# LED_Schaltung.net
KiCad netlist of a schematic drawn in EAGLE
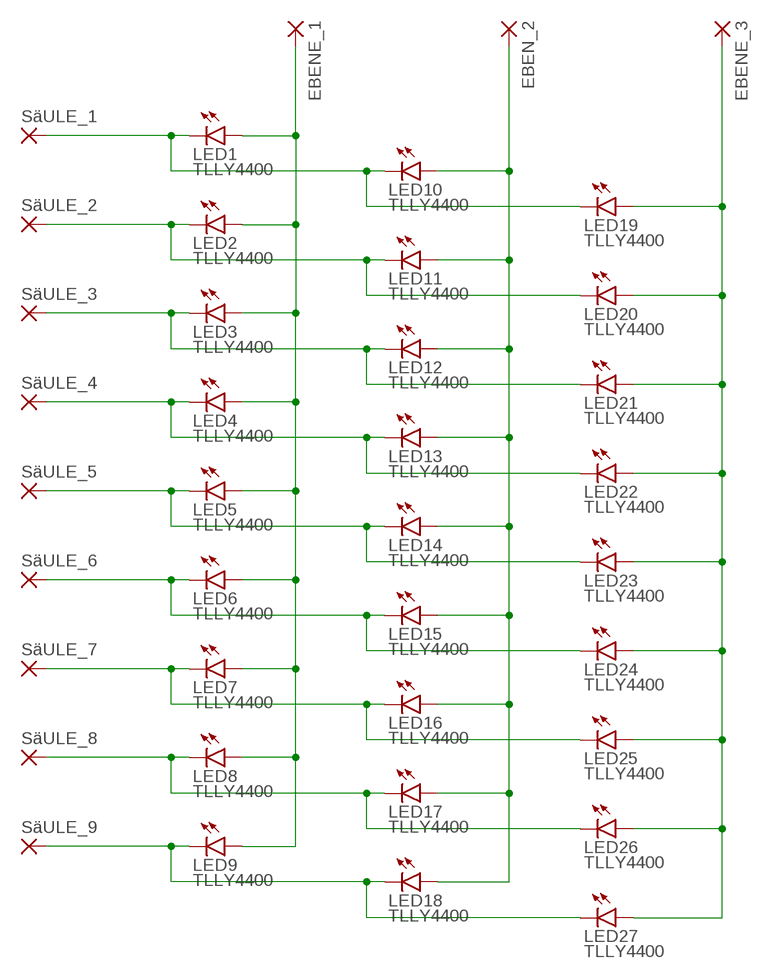
[diagram p0: schematic, sheet 1]

(export (version "E")
  (design (tool "Eeschema 10.0.6"))
  (components
    (comp (ref "EBENE_1")
      (value "2,54/1,0")
      (footprint "eagle-import:2,54_1,0")
      (libsource (lib "eagle-import") (part "2,54/1,0"))
    )
    (comp (ref "EBENE_3")
      (value "2,54/1,0")
      (footprint "eagle-import:2,54_1,0")
      (libsource (lib "eagle-import") (part "2,54/1,0"))
    )
    (comp (ref "EBEN_2")
      (value "2,54/1,0")
      (footprint "eagle-import:2,54_1,0")
      (libsource (lib "eagle-import") (part "2,54/1,0"))
    )
    (comp (ref "LED1")
      (value "TLLY4400")
      (footprint "eagle-import:LED3MM")
      (fields (field (name "MF") "VISHAY SEMICONDUCTOR"))
      (libsource (lib "eagle-import") (part "TLLY4400"))
    )
    (comp (ref "LED2")
      (value "TLLY4400")
      (footprint "eagle-import:LED3MM")
      (fields (field (name "MF") "VISHAY SEMICONDUCTOR"))
      (libsource (lib "eagle-import") (part "TLLY4400"))
    )
    (comp (ref "LED3")
      (value "TLLY4400")
      (footprint "eagle-import:LED3MM")
      (fields (field (name "MF") "VISHAY SEMICONDUCTOR"))
      (libsource (lib "eagle-import") (part "TLLY4400"))
    )
    (comp (ref "LED4")
      (value "TLLY4400")
      (footprint "eagle-import:LED3MM")
      (fields (field (name "MF") "VISHAY SEMICONDUCTOR"))
      (libsource (lib "eagle-import") (part "TLLY4400"))
    )
    (comp (ref "LED5")
      (value "TLLY4400")
      (footprint "eagle-import:LED3MM")
      (fields (field (name "MF") "VISHAY SEMICONDUCTOR"))
      (libsource (lib "eagle-import") (part "TLLY4400"))
    )
    (comp (ref "LED6")
      (value "TLLY4400")
      (footprint "eagle-import:LED3MM")
      (fields (field (name "MF") "VISHAY SEMICONDUCTOR"))
      (libsource (lib "eagle-import") (part "TLLY4400"))
    )
    (comp (ref "LED7")
      (value "TLLY4400")
      (footprint "eagle-import:LED3MM")
      (fields (field (name "MF") "VISHAY SEMICONDUCTOR"))
      (libsource (lib "eagle-import") (part "TLLY4400"))
    )
    (comp (ref "LED8")
      (value "TLLY4400")
      (footprint "eagle-import:LED3MM")
      (fields (field (name "MF") "VISHAY SEMICONDUCTOR"))
      (libsource (lib "eagle-import") (part "TLLY4400"))
    )
    (comp (ref "LED9")
      (value "TLLY4400")
      (footprint "eagle-import:LED3MM")
      (fields (field (name "MF") "VISHAY SEMICONDUCTOR"))
      (libsource (lib "eagle-import") (part "TLLY4400"))
    )
    (comp (ref "LED10")
      (value "TLLY4400")
      (footprint "eagle-import:LED3MM")
      (fields (field (name "MF") "VISHAY SEMICONDUCTOR"))
      (libsource (lib "eagle-import") (part "TLLY4400"))
    )
    (comp (ref "LED11")
      (value "TLLY4400")
      (footprint "eagle-import:LED3MM")
      (fields (field (name "MF") "VISHAY SEMICONDUCTOR"))
      (libsource (lib "eagle-import") (part "TLLY4400"))
    )
    (comp (ref "LED12")
      (value "TLLY4400")
      (footprint "eagle-import:LED3MM")
      (fields (field (name "MF") "VISHAY SEMICONDUCTOR"))
      (libsource (lib "eagle-import") (part "TLLY4400"))
    )
    (comp (ref "LED13")
      (value "TLLY4400")
      (footprint "eagle-import:LED3MM")
      (fields (field (name "MF") "VISHAY SEMICONDUCTOR"))
      (libsource (lib "eagle-import") (part "TLLY4400"))
    )
    (comp (ref "LED14")
      (value "TLLY4400")
      (footprint "eagle-import:LED3MM")
      (fields (field (name "MF") "VISHAY SEMICONDUCTOR"))
      (libsource (lib "eagle-import") (part "TLLY4400"))
    )
    (comp (ref "LED15")
      (value "TLLY4400")
      (footprint "eagle-import:LED3MM")
      (fields (field (name "MF") "VISHAY SEMICONDUCTOR"))
      (libsource (lib "eagle-import") (part "TLLY4400"))
    )
    (comp (ref "LED16")
      (value "TLLY4400")
      (footprint "eagle-import:LED3MM")
      (fields (field (name "MF") "VISHAY SEMICONDUCTOR"))
      (libsource (lib "eagle-import") (part "TLLY4400"))
    )
    (comp (ref "LED17")
      (value "TLLY4400")
      (footprint "eagle-import:LED3MM")
      (fields (field (name "MF") "VISHAY SEMICONDUCTOR"))
      (libsource (lib "eagle-import") (part "TLLY4400"))
    )
    (comp (ref "LED18")
      (value "TLLY4400")
      (footprint "eagle-import:LED3MM")
      (fields (field (name "MF") "VISHAY SEMICONDUCTOR"))
      (libsource (lib "eagle-import") (part "TLLY4400"))
    )
    (comp (ref "LED19")
      (value "TLLY4400")
      (footprint "eagle-import:LED3MM")
      (fields (field (name "MF") "VISHAY SEMICONDUCTOR"))
      (libsource (lib "eagle-import") (part "TLLY4400"))
    )
    (comp (ref "LED20")
      (value "TLLY4400")
      (footprint "eagle-import:LED3MM")
      (fields (field (name "MF") "VISHAY SEMICONDUCTOR"))
      (libsource (lib "eagle-import") (part "TLLY4400"))
    )
    (comp (ref "LED21")
      (value "TLLY4400")
      (footprint "eagle-import:LED3MM")
      (fields (field (name "MF") "VISHAY SEMICONDUCTOR"))
      (libsource (lib "eagle-import") (part "TLLY4400"))
    )
    (comp (ref "LED22")
      (value "TLLY4400")
      (footprint "eagle-import:LED3MM")
      (fields (field (name "MF") "VISHAY SEMICONDUCTOR"))
      (libsource (lib "eagle-import") (part "TLLY4400"))
    )
    (comp (ref "LED23")
      (value "TLLY4400")
      (footprint "eagle-import:LED3MM")
      (fields (field (name "MF") "VISHAY SEMICONDUCTOR"))
      (libsource (lib "eagle-import") (part "TLLY4400"))
    )
    (comp (ref "LED24")
      (value "TLLY4400")
      (footprint "eagle-import:LED3MM")
      (fields (field (name "MF") "VISHAY SEMICONDUCTOR"))
      (libsource (lib "eagle-import") (part "TLLY4400"))
    )
    (comp (ref "LED25")
      (value "TLLY4400")
      (footprint "eagle-import:LED3MM")
      (fields (field (name "MF") "VISHAY SEMICONDUCTOR"))
      (libsource (lib "eagle-import") (part "TLLY4400"))
    )
    (comp (ref "LED26")
      (value "TLLY4400")
      (footprint "eagle-import:LED3MM")
      (fields (field (name "MF") "VISHAY SEMICONDUCTOR"))
      (libsource (lib "eagle-import") (part "TLLY4400"))
    )
    (comp (ref "LED27")
      (value "TLLY4400")
      (footprint "eagle-import:LED3MM")
      (fields (field (name "MF") "VISHAY SEMICONDUCTOR"))
      (libsource (lib "eagle-import") (part "TLLY4400"))
    )
    (comp (ref "SäULE_1")
      (value "2,54/1,0")
      (footprint "eagle-import:2,54_1,0")
      (libsource (lib "eagle-import") (part "2,54/1,0"))
    )
    (comp (ref "SäULE_2")
      (value "2,54/1,0")
      (footprint "eagle-import:2,54_1,0")
      (libsource (lib "eagle-import") (part "2,54/1,0"))
    )
    (comp (ref "SäULE_3")
      (value "2,54/1,0")
      (footprint "eagle-import:2,54_1,0")
      (libsource (lib "eagle-import") (part "2,54/1,0"))
    )
    (comp (ref "SäULE_4")
      (value "2,54/1,0")
      (footprint "eagle-import:2,54_1,0")
      (libsource (lib "eagle-import") (part "2,54/1,0"))
    )
    (comp (ref "SäULE_5")
      (value "2,54/1,0")
      (footprint "eagle-import:2,54_1,0")
      (libsource (lib "eagle-import") (part "2,54/1,0"))
    )
    (comp (ref "SäULE_6")
      (value "2,54/1,0")
      (footprint "eagle-import:2,54_1,0")
      (libsource (lib "eagle-import") (part "2,54/1,0"))
    )
    (comp (ref "SäULE_7")
      (value "2,54/1,0")
      (footprint "eagle-import:2,54_1,0")
      (libsource (lib "eagle-import") (part "2,54/1,0"))
    )
    (comp (ref "SäULE_8")
      (value "2,54/1,0")
      (footprint "eagle-import:2,54_1,0")
      (libsource (lib "eagle-import") (part "2,54/1,0"))
    )
    (comp (ref "SäULE_9")
      (value "2,54/1,0")
      (footprint "eagle-import:2,54_1,0")
      (libsource (lib "eagle-import") (part "2,54/1,0"))
    )
  )
  (nets
    (net (code "1") (name "Net-(EBENE_1-P)") (class "Default")
      (node (ref "EBENE_1") (pin "1") (pinfunction "P_1") (pintype "passive"))
      (node (ref "LED1") (pin "A") (pinfunction "A_A") (pintype "passive"))
      (node (ref "LED2") (pin "A") (pinfunction "A_A") (pintype "passive"))
      (node (ref "LED3") (pin "A") (pinfunction "A_A") (pintype "passive"))
      (node (ref "LED4") (pin "A") (pinfunction "A_A") (pintype "passive"))
      (node (ref "LED5") (pin "A") (pinfunction "A_A") (pintype "passive"))
      (node (ref "LED6") (pin "A") (pinfunction "A_A") (pintype "passive"))
      (node (ref "LED7") (pin "A") (pinfunction "A_A") (pintype "passive"))
      (node (ref "LED8") (pin "A") (pinfunction "A_A") (pintype "passive"))
      (node (ref "LED9") (pin "A") (pinfunction "A_A") (pintype "passive"))
    )
    (net (code "2") (name "Net-(EBENE_3-P)") (class "Default")
      (node (ref "EBENE_3") (pin "1") (pinfunction "P_1") (pintype "passive"))
      (node (ref "LED19") (pin "A") (pinfunction "A_A") (pintype "passive"))
      (node (ref "LED20") (pin "A") (pinfunction "A_A") (pintype "passive"))
      (node (ref "LED21") (pin "A") (pinfunction "A_A") (pintype "passive"))
      (node (ref "LED22") (pin "A") (pinfunction "A_A") (pintype "passive"))
      (node (ref "LED23") (pin "A") (pinfunction "A_A") (pintype "passive"))
      (node (ref "LED24") (pin "A") (pinfunction "A_A") (pintype "passive"))
      (node (ref "LED25") (pin "A") (pinfunction "A_A") (pintype "passive"))
      (node (ref "LED26") (pin "A") (pinfunction "A_A") (pintype "passive"))
      (node (ref "LED27") (pin "A") (pinfunction "A_A") (pintype "passive"))
    )
    (net (code "3") (name "Net-(EBEN_2-P)") (class "Default")
      (node (ref "EBEN_2") (pin "1") (pinfunction "P_1") (pintype "passive"))
      (node (ref "LED10") (pin "A") (pinfunction "A_A") (pintype "passive"))
      (node (ref "LED11") (pin "A") (pinfunction "A_A") (pintype "passive"))
      (node (ref "LED12") (pin "A") (pinfunction "A_A") (pintype "passive"))
      (node (ref "LED13") (pin "A") (pinfunction "A_A") (pintype "passive"))
      (node (ref "LED14") (pin "A") (pinfunction "A_A") (pintype "passive"))
      (node (ref "LED15") (pin "A") (pinfunction "A_A") (pintype "passive"))
      (node (ref "LED16") (pin "A") (pinfunction "A_A") (pintype "passive"))
      (node (ref "LED17") (pin "A") (pinfunction "A_A") (pintype "passive"))
      (node (ref "LED18") (pin "A") (pinfunction "A_A") (pintype "passive"))
    )
    (net (code "4") (name "Net-(LED1-C)") (class "Default")
      (node (ref "LED1") (pin "K") (pinfunction "C_K") (pintype "passive"))
      (node (ref "LED10") (pin "K") (pinfunction "C_K") (pintype "passive"))
      (node (ref "LED19") (pin "K") (pinfunction "C_K") (pintype "passive"))
      (node (ref "SäULE_1") (pin "1") (pinfunction "P_1") (pintype "passive"))
    )
    (net (code "5") (name "Net-(LED11-C)") (class "Default")
      (node (ref "LED11") (pin "K") (pinfunction "C_K") (pintype "passive"))
      (node (ref "LED2") (pin "K") (pinfunction "C_K") (pintype "passive"))
      (node (ref "LED20") (pin "K") (pinfunction "C_K") (pintype "passive"))
      (node (ref "SäULE_2") (pin "1") (pinfunction "P_1") (pintype "passive"))
    )
    (net (code "6") (name "Net-(LED12-C)") (class "Default")
      (node (ref "LED12") (pin "K") (pinfunction "C_K") (pintype "passive"))
      (node (ref "LED21") (pin "K") (pinfunction "C_K") (pintype "passive"))
      (node (ref "LED3") (pin "K") (pinfunction "C_K") (pintype "passive"))
      (node (ref "SäULE_3") (pin "1") (pinfunction "P_1") (pintype "passive"))
    )
    (net (code "7") (name "Net-(LED13-C)") (class "Default")
      (node (ref "LED13") (pin "K") (pinfunction "C_K") (pintype "passive"))
      (node (ref "LED22") (pin "K") (pinfunction "C_K") (pintype "passive"))
      (node (ref "LED4") (pin "K") (pinfunction "C_K") (pintype "passive"))
      (node (ref "SäULE_4") (pin "1") (pinfunction "P_1") (pintype "passive"))
    )
    (net (code "8") (name "Net-(LED14-C)") (class "Default")
      (node (ref "LED14") (pin "K") (pinfunction "C_K") (pintype "passive"))
      (node (ref "LED23") (pin "K") (pinfunction "C_K") (pintype "passive"))
      (node (ref "LED5") (pin "K") (pinfunction "C_K") (pintype "passive"))
      (node (ref "SäULE_5") (pin "1") (pinfunction "P_1") (pintype "passive"))
    )
    (net (code "9") (name "Net-(LED15-C)") (class "Default")
      (node (ref "LED15") (pin "K") (pinfunction "C_K") (pintype "passive"))
      (node (ref "LED24") (pin "K") (pinfunction "C_K") (pintype "passive"))
      (node (ref "LED6") (pin "K") (pinfunction "C_K") (pintype "passive"))
      (node (ref "SäULE_6") (pin "1") (pinfunction "P_1") (pintype "passive"))
    )
    (net (code "10") (name "Net-(LED16-C)") (class "Default")
      (node (ref "LED16") (pin "K") (pinfunction "C_K") (pintype "passive"))
      (node (ref "LED25") (pin "K") (pinfunction "C_K") (pintype "passive"))
      (node (ref "LED7") (pin "K") (pinfunction "C_K") (pintype "passive"))
      (node (ref "SäULE_7") (pin "1") (pinfunction "P_1") (pintype "passive"))
    )
    (net (code "11") (name "Net-(LED17-C)") (class "Default")
      (node (ref "LED17") (pin "K") (pinfunction "C_K") (pintype "passive"))
      (node (ref "LED26") (pin "K") (pinfunction "C_K") (pintype "passive"))
      (node (ref "LED8") (pin "K") (pinfunction "C_K") (pintype "passive"))
      (node (ref "SäULE_8") (pin "1") (pinfunction "P_1") (pintype "passive"))
    )
    (net (code "12") (name "Net-(LED18-C)") (class "Default")
      (node (ref "LED18") (pin "K") (pinfunction "C_K") (pintype "passive"))
      (node (ref "LED27") (pin "K") (pinfunction "C_K") (pintype "passive"))
      (node (ref "LED9") (pin "K") (pinfunction "C_K") (pintype "passive"))
      (node (ref "SäULE_9") (pin "1") (pinfunction "P_1") (pintype "passive"))
    )
  )
)
